# Sensor_Acquisition_Board_Rev4.net
KiCad netlist of a schematic drawn in EAGLE
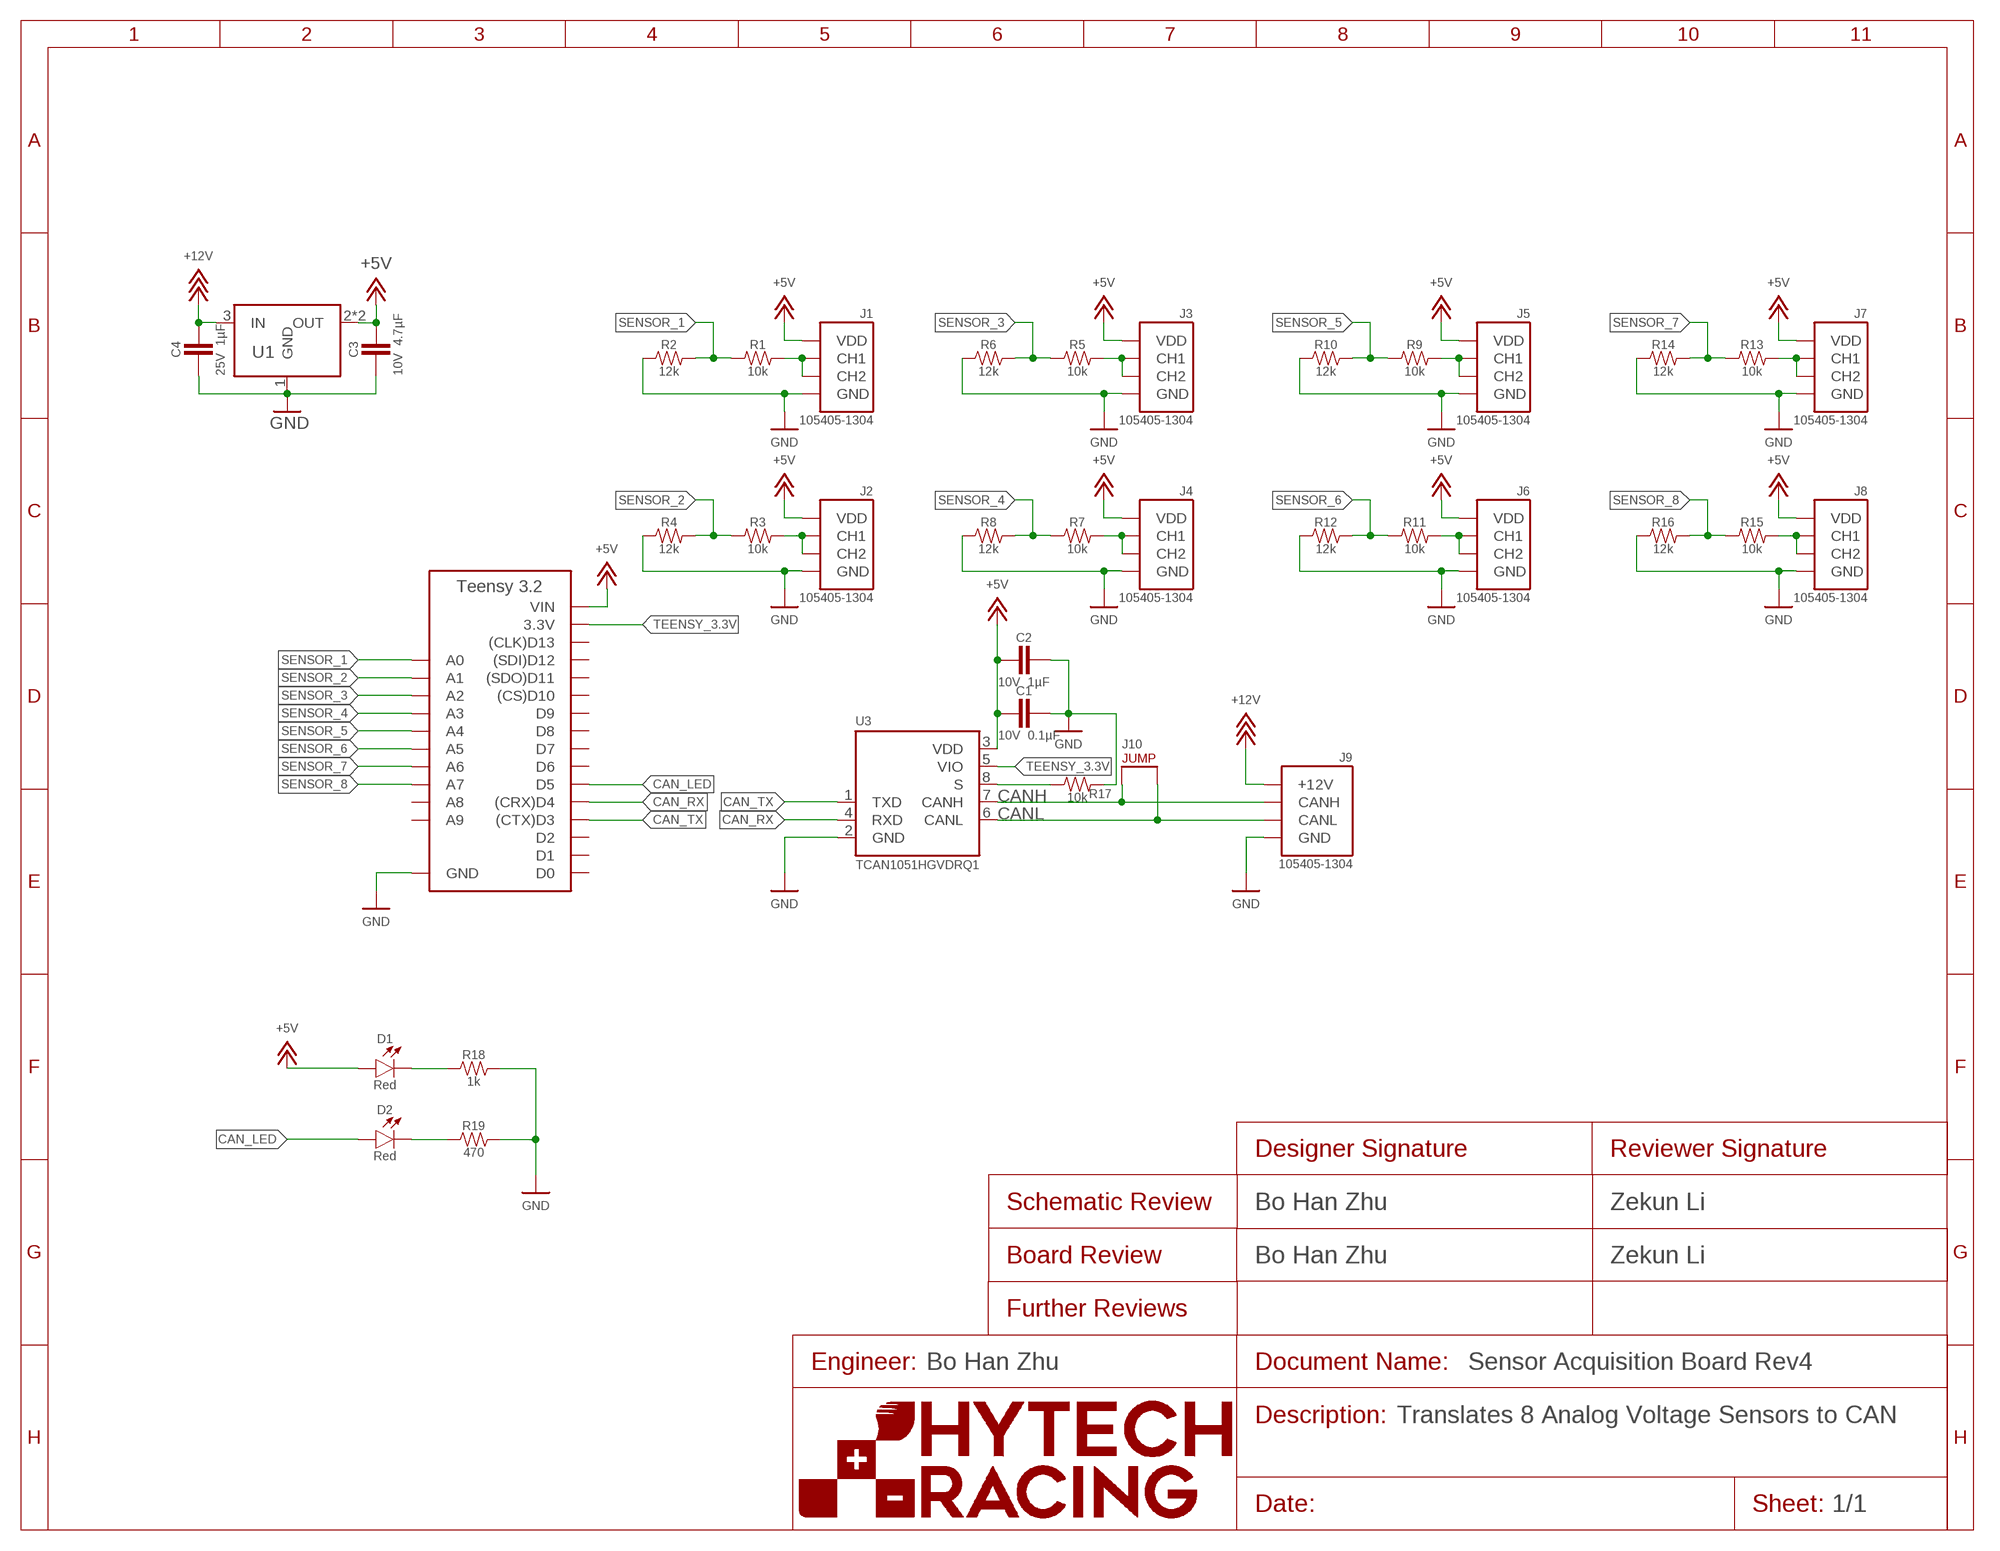
[diagram p0: schematic, sheet 1]

(export (version "E")
  (design (tool "Eeschema 10.0.6"))
  (components
    (comp (ref "A1")
      (value "TEENSY_3.2")
      (footprint "eagle-import:TEENSY_SHORT")
      (libsource (lib "eagle-import") (part "TEENSY_3.2"))
    )
    (comp (ref "C1")
      (value "CAPACITOR_0603_10V_0.1UF")
      (footprint "eagle-import:0603-CAP")
      (fields
        (field (name "CAPACITANCE") "0.1µF")
        (field (name "MANUFACTURER") "Vishay Vitramon")
        (field (name "MPN") "VJ0603Y104JXQPW1BC")
        (field (name "TOLERANCE") "5%")
        (field (name "VOLTAGE") "10V")
      )
      (libsource (lib "eagle-import") (part "CAPACITOR_?_060310V_0.1UF"))
    )
    (comp (ref "C2")
      (value "CAPACITOR_0603_10V_1UF")
      (footprint "eagle-import:0603-CAP")
      (fields
        (field (name "CAPACITANCE") "1µF")
        (field (name "MANUFACTURER") "Yageo")
        (field (name "MPN") "CC0603KRX7R6BB105")
        (field (name "TOLERANCE") "10%")
        (field (name "VOLTAGE") "10V")
      )
      (libsource (lib "eagle-import") (part "CAPACITOR_?_060310V_1UF"))
    )
    (comp (ref "C3")
      (value "CAPACITOR_0603_10V_4.7UF")
      (footprint "eagle-import:0603-CAP")
      (fields
        (field (name "CAPACITANCE") "4.7µF")
        (field (name "MANUFACTURER") "Samsung Electro-Mechanics")
        (field (name "MPN") "CL10A475KP8NNNC")
        (field (name "TOLERANCE") "10%")
        (field (name "VOLTAGE") "10V")
      )
      (libsource (lib "eagle-import") (part "CAPACITOR_?_060310V_4.7UF"))
    )
    (comp (ref "C4")
      (value "CAPACITOR_0603_25V_1UF")
      (footprint "eagle-import:0603-CAP")
      (fields
        (field (name "CAPACITANCE") "1µF")
        (field (name "MANUFACTURER") "Samsung Electro-Mechanics")
        (field (name "MPN") "CL10B105KA8NNNC")
        (field (name "TOLERANCE") "10%")
        (field (name "VOLTAGE") "25V")
      )
      (libsource (lib "eagle-import") (part "CAPACITOR_?_060325V_1UF"))
    )
    (comp (ref "D1")
      (value "LED_0603_RED")
      (footprint "eagle-import:0603-LED")
      (fields
        (field (name "COLOR") "Red")
        (field (name "MANUFACTURER") "Kingbright")
        (field (name "MPN") "APT1608SECK/J3-PRV")
      )
      (libsource (lib "eagle-import") (part "LED_?_0603RED"))
    )
    (comp (ref "D2")
      (value "LED_0603_RED")
      (footprint "eagle-import:0603-LED")
      (fields
        (field (name "COLOR") "Red")
        (field (name "MANUFACTURER") "Kingbright")
        (field (name "MPN") "APT1608SECK/J3-PRV")
      )
      (libsource (lib "eagle-import") (part "LED_?_0603RED"))
    )
    (comp (ref "J1")
      (value "CONNECTOR-SENSOR_NF_S_RA_BLACK")
      (footprint "eagle-import:MOLEX_NANOFIT_SMD_RIGHTANGLE_04")
      (fields (field (name "MANUFACTURER") "Molex") (field (name "MPN") "105405-1304"))
      (libsource (lib "eagle-import") (part "CONNECTOR-SENSOR_?_NF_S_RABLACK"))
    )
    (comp (ref "J2")
      (value "CONNECTOR-SENSOR_NF_S_RA_BLACK")
      (footprint "eagle-import:MOLEX_NANOFIT_SMD_RIGHTANGLE_04")
      (fields (field (name "MANUFACTURER") "Molex") (field (name "MPN") "105405-1304"))
      (libsource (lib "eagle-import") (part "CONNECTOR-SENSOR_?_NF_S_RABLACK"))
    )
    (comp (ref "J3")
      (value "CONNECTOR-SENSOR_NF_S_RA_BLACK")
      (footprint "eagle-import:MOLEX_NANOFIT_SMD_RIGHTANGLE_04")
      (fields (field (name "MANUFACTURER") "Molex") (field (name "MPN") "105405-1304"))
      (libsource (lib "eagle-import") (part "CONNECTOR-SENSOR_?_NF_S_RABLACK"))
    )
    (comp (ref "J4")
      (value "CONNECTOR-SENSOR_NF_S_RA_BLACK")
      (footprint "eagle-import:MOLEX_NANOFIT_SMD_RIGHTANGLE_04")
      (fields (field (name "MANUFACTURER") "Molex") (field (name "MPN") "105405-1304"))
      (libsource (lib "eagle-import") (part "CONNECTOR-SENSOR_?_NF_S_RABLACK"))
    )
    (comp (ref "J5")
      (value "CONNECTOR-SENSOR_NF_S_RA_BLACK")
      (footprint "eagle-import:MOLEX_NANOFIT_SMD_RIGHTANGLE_04")
      (fields (field (name "MANUFACTURER") "Molex") (field (name "MPN") "105405-1304"))
      (libsource (lib "eagle-import") (part "CONNECTOR-SENSOR_?_NF_S_RABLACK"))
    )
    (comp (ref "J6")
      (value "CONNECTOR-SENSOR_NF_S_RA_BLACK")
      (footprint "eagle-import:MOLEX_NANOFIT_SMD_RIGHTANGLE_04")
      (fields (field (name "MANUFACTURER") "Molex") (field (name "MPN") "105405-1304"))
      (libsource (lib "eagle-import") (part "CONNECTOR-SENSOR_?_NF_S_RABLACK"))
    )
    (comp (ref "J7")
      (value "CONNECTOR-SENSOR_NF_S_RA_BLACK")
      (footprint "eagle-import:MOLEX_NANOFIT_SMD_RIGHTANGLE_04")
      (fields (field (name "MANUFACTURER") "Molex") (field (name "MPN") "105405-1304"))
      (libsource (lib "eagle-import") (part "CONNECTOR-SENSOR_?_NF_S_RABLACK"))
    )
    (comp (ref "J8")
      (value "CONNECTOR-SENSOR_NF_S_RA_BLACK")
      (footprint "eagle-import:MOLEX_NANOFIT_SMD_RIGHTANGLE_04")
      (fields (field (name "MANUFACTURER") "Molex") (field (name "MPN") "105405-1304"))
      (libsource (lib "eagle-import") (part "CONNECTOR-SENSOR_?_NF_S_RABLACK"))
    )
    (comp (ref "J9")
      (value "CONNECTOR-CAN_NF_S_RA_BLACK")
      (footprint "eagle-import:MOLEX_NANOFIT_SMD_RIGHTANGLE_04")
      (fields (field (name "MANUFACTURER") "Molex") (field (name "MPN") "105405-1304"))
      (libsource (lib "eagle-import") (part "CONNECTOR-CAN_?_NF_S_RABLACK"))
    )
    (comp (ref "J10")
      (value "JUMPER_1X02_")
      (footprint "eagle-import:1X02")
      (libsource (lib "eagle-import") (part "JUMPER_?_1X02"))
    )
    (comp (ref "R1")
      (value "RESISTOR_0603_10K")
      (footprint "eagle-import:0603-RES")
      (fields
        (field (name "MANUFACTURER") "Yageo")
        (field (name "MPN") "RC0603FR-0710KL")
        (field (name "POWER") "0.1W")
        (field (name "RESISTANCE") "10k")
      )
      (libsource (lib "eagle-import") (part "RESISTOR_?_060310K"))
    )
    (comp (ref "R2")
      (value "RESISTOR_0603_12K")
      (footprint "eagle-import:0603-RES")
      (fields
        (field (name "MANUFACTURER") "Yageo")
        (field (name "MPN") "RC0603FR-0712KL")
        (field (name "POWER") "0.1W")
        (field (name "RESISTANCE") "12k")
      )
      (libsource (lib "eagle-import") (part "RESISTOR_?_060312K"))
    )
    (comp (ref "R3")
      (value "RESISTOR_0603_10K")
      (footprint "eagle-import:0603-RES")
      (fields
        (field (name "MANUFACTURER") "Yageo")
        (field (name "MPN") "RC0603FR-0710KL")
        (field (name "POWER") "0.1W")
        (field (name "RESISTANCE") "10k")
      )
      (libsource (lib "eagle-import") (part "RESISTOR_?_060310K"))
    )
    (comp (ref "R4")
      (value "RESISTOR_0603_12K")
      (footprint "eagle-import:0603-RES")
      (fields
        (field (name "MANUFACTURER") "Yageo")
        (field (name "MPN") "RC0603FR-0712KL")
        (field (name "POWER") "0.1W")
        (field (name "RESISTANCE") "12k")
      )
      (libsource (lib "eagle-import") (part "RESISTOR_?_060312K"))
    )
    (comp (ref "R5")
      (value "RESISTOR_0603_10K")
      (footprint "eagle-import:0603-RES")
      (fields
        (field (name "MANUFACTURER") "Yageo")
        (field (name "MPN") "RC0603FR-0710KL")
        (field (name "POWER") "0.1W")
        (field (name "RESISTANCE") "10k")
      )
      (libsource (lib "eagle-import") (part "RESISTOR_?_060310K"))
    )
    (comp (ref "R6")
      (value "RESISTOR_0603_12K")
      (footprint "eagle-import:0603-RES")
      (fields
        (field (name "MANUFACTURER") "Yageo")
        (field (name "MPN") "RC0603FR-0712KL")
        (field (name "POWER") "0.1W")
        (field (name "RESISTANCE") "12k")
      )
      (libsource (lib "eagle-import") (part "RESISTOR_?_060312K"))
    )
    (comp (ref "R7")
      (value "RESISTOR_0603_10K")
      (footprint "eagle-import:0603-RES")
      (fields
        (field (name "MANUFACTURER") "Yageo")
        (field (name "MPN") "RC0603FR-0710KL")
        (field (name "POWER") "0.1W")
        (field (name "RESISTANCE") "10k")
      )
      (libsource (lib "eagle-import") (part "RESISTOR_?_060310K"))
    )
    (comp (ref "R8")
      (value "RESISTOR_0603_12K")
      (footprint "eagle-import:0603-RES")
      (fields
        (field (name "MANUFACTURER") "Yageo")
        (field (name "MPN") "RC0603FR-0712KL")
        (field (name "POWER") "0.1W")
        (field (name "RESISTANCE") "12k")
      )
      (libsource (lib "eagle-import") (part "RESISTOR_?_060312K"))
    )
    (comp (ref "R9")
      (value "RESISTOR_0603_10K")
      (footprint "eagle-import:0603-RES")
      (fields
        (field (name "MANUFACTURER") "Yageo")
        (field (name "MPN") "RC0603FR-0710KL")
        (field (name "POWER") "0.1W")
        (field (name "RESISTANCE") "10k")
      )
      (libsource (lib "eagle-import") (part "RESISTOR_?_060310K"))
    )
    (comp (ref "R10")
      (value "RESISTOR_0603_12K")
      (footprint "eagle-import:0603-RES")
      (fields
        (field (name "MANUFACTURER") "Yageo")
        (field (name "MPN") "RC0603FR-0712KL")
        (field (name "POWER") "0.1W")
        (field (name "RESISTANCE") "12k")
      )
      (libsource (lib "eagle-import") (part "RESISTOR_?_060312K"))
    )
    (comp (ref "R11")
      (value "RESISTOR_0603_10K")
      (footprint "eagle-import:0603-RES")
      (fields
        (field (name "MANUFACTURER") "Yageo")
        (field (name "MPN") "RC0603FR-0710KL")
        (field (name "POWER") "0.1W")
        (field (name "RESISTANCE") "10k")
      )
      (libsource (lib "eagle-import") (part "RESISTOR_?_060310K"))
    )
    (comp (ref "R12")
      (value "RESISTOR_0603_12K")
      (footprint "eagle-import:0603-RES")
      (fields
        (field (name "MANUFACTURER") "Yageo")
        (field (name "MPN") "RC0603FR-0712KL")
        (field (name "POWER") "0.1W")
        (field (name "RESISTANCE") "12k")
      )
      (libsource (lib "eagle-import") (part "RESISTOR_?_060312K"))
    )
    (comp (ref "R13")
      (value "RESISTOR_0603_10K")
      (footprint "eagle-import:0603-RES")
      (fields
        (field (name "MANUFACTURER") "Yageo")
        (field (name "MPN") "RC0603FR-0710KL")
        (field (name "POWER") "0.1W")
        (field (name "RESISTANCE") "10k")
      )
      (libsource (lib "eagle-import") (part "RESISTOR_?_060310K"))
    )
    (comp (ref "R14")
      (value "RESISTOR_0603_12K")
      (footprint "eagle-import:0603-RES")
      (fields
        (field (name "MANUFACTURER") "Yageo")
        (field (name "MPN") "RC0603FR-0712KL")
        (field (name "POWER") "0.1W")
        (field (name "RESISTANCE") "12k")
      )
      (libsource (lib "eagle-import") (part "RESISTOR_?_060312K"))
    )
    (comp (ref "R15")
      (value "RESISTOR_0603_10K")
      (footprint "eagle-import:0603-RES")
      (fields
        (field (name "MANUFACTURER") "Yageo")
        (field (name "MPN") "RC0603FR-0710KL")
        (field (name "POWER") "0.1W")
        (field (name "RESISTANCE") "10k")
      )
      (libsource (lib "eagle-import") (part "RESISTOR_?_060310K"))
    )
    (comp (ref "R16")
      (value "RESISTOR_0603_12K")
      (footprint "eagle-import:0603-RES")
      (fields
        (field (name "MANUFACTURER") "Yageo")
        (field (name "MPN") "RC0603FR-0712KL")
        (field (name "POWER") "0.1W")
        (field (name "RESISTANCE") "12k")
      )
      (libsource (lib "eagle-import") (part "RESISTOR_?_060312K"))
    )
    (comp (ref "R17")
      (value "RESISTOR_0603_10K")
      (footprint "eagle-import:0603-RES")
      (fields
        (field (name "MANUFACTURER") "Yageo")
        (field (name "MPN") "RC0603FR-0710KL")
        (field (name "POWER") "0.1W")
        (field (name "RESISTANCE") "10k")
      )
      (libsource (lib "eagle-import") (part "RESISTOR_?_060310K"))
    )
    (comp (ref "R18")
      (value "RESISTOR_0603_1K")
      (footprint "eagle-import:0603-RES")
      (fields
        (field (name "MANUFACTURER") "Yageo")
        (field (name "MPN") "RC0603FR-071KL")
        (field (name "POWER") "0.1W")
        (field (name "RESISTANCE") "1k")
      )
      (libsource (lib "eagle-import") (part "RESISTOR_?_06031K"))
    )
    (comp (ref "R19")
      (value "RESISTOR_0603_470")
      (footprint "eagle-import:0603-RES")
      (fields
        (field (name "MANUFACTURER") "Panasonic Electronic Components")
        (field (name "MPN") "ERJ-PA3F4700V")
        (field (name "POWER") "0.25W")
        (field (name "RESISTANCE") "470")
      )
      (libsource (lib "eagle-import") (part "RESISTOR_?_0603470"))
    )
    (comp (ref "U1")
      (value "VOLTAGE_REGULATOR_SOT223_5V")
      (footprint "eagle-import:SOT223")
      (fields (field (name "MANUFACTURER") "STMicroelectronics") (field (name "MPN") "LDL1117S50R"))
      (libsource (lib "eagle-import") (part "VOLTAGE_REGULATOR_?_SOT2235V"))
    )
    (comp (ref "U3")
      (value "TCAN1051HQV-Q1")
      (footprint "eagle-import:SOIC-08(NARROW,0.15_)")
      (fields (field (name "MANUFACTURER") "Texas Instruments") (field (name "MPN") "TCAN1051HGVDRQ1"))
      (libsource (lib "eagle-import") (part "TCAN1051V-Q1HQ"))
    )
  )
  (nets
    (net (code "1") (name "+5V") (class "Default")
      (node (ref "A1") (pin "VIN") (pinfunction "VIN_VIN") (pintype "power_in"))
      (node (ref "C1") (pin "2") (pinfunction "2_2") (pintype "passive"))
      (node (ref "C2") (pin "2") (pinfunction "2_2") (pintype "passive"))
      (node (ref "C3") (pin "1") (pinfunction "1_1") (pintype "passive"))
      (node (ref "D1") (pin "2") (pinfunction "A_2") (pintype "passive"))
      (node (ref "J1") (pin "1") (pinfunction "VDD_1") (pintype "power_in"))
      (node (ref "J2") (pin "1") (pinfunction "VDD_1") (pintype "power_in"))
      (node (ref "J3") (pin "1") (pinfunction "VDD_1") (pintype "power_in"))
      (node (ref "J4") (pin "1") (pinfunction "VDD_1") (pintype "power_in"))
      (node (ref "J5") (pin "1") (pinfunction "VDD_1") (pintype "power_in"))
      (node (ref "J6") (pin "1") (pinfunction "VDD_1") (pintype "power_in"))
      (node (ref "J7") (pin "1") (pinfunction "VDD_1") (pintype "power_in"))
      (node (ref "J8") (pin "1") (pinfunction "VDD_1") (pintype "power_in"))
      (node (ref "U1") (pin "2") (pinfunction "OUT_2") (pintype "power_in"))
      (node (ref "U1") (pin "4") (pinfunction "OUT_4") (pintype "power_in"))
      (node (ref "U3") (pin "3") (pinfunction "VDD_3") (pintype "power_in"))
    )
    (net (code "2") (name "+12V") (class "Default")
      (node (ref "C4") (pin "1") (pinfunction "1_1") (pintype "passive"))
      (node (ref "J9") (pin "1") (pinfunction "+12V_1") (pintype "power_in"))
      (node (ref "U1") (pin "3") (pinfunction "IN_3") (pintype "power_in"))
    )
    (net (code "3") (name "/CANH") (class "Default")
      (node (ref "J10") (pin "1") (pinfunction "P$1_1") (pintype "passive"))
      (node (ref "J9") (pin "4") (pinfunction "CANH_4") (pintype "bidirectional"))
      (node (ref "U3") (pin "7") (pinfunction "CANH_7") (pintype "output"))
    )
    (net (code "4") (name "/CANL") (class "Default")
      (node (ref "J10") (pin "2") (pinfunction "P$2_2") (pintype "passive"))
      (node (ref "J9") (pin "3") (pinfunction "CANL_3") (pintype "bidirectional"))
      (node (ref "U3") (pin "6") (pinfunction "CANL_6") (pintype "bidirectional"))
    )
    (net (code "5") (name "CAN_LED") (class "Default")
      (node (ref "A1") (pin "D5") (pinfunction "D5_D5") (pintype "bidirectional"))
      (node (ref "D2") (pin "2") (pinfunction "A_2") (pintype "passive"))
    )
    (net (code "6") (name "CAN_RX") (class "Default")
      (node (ref "A1") (pin "D4") (pinfunction "(CRX)D4_D4") (pintype "bidirectional"))
      (node (ref "U3") (pin "4") (pinfunction "RXD_4") (pintype "output"))
    )
    (net (code "7") (name "CAN_TX") (class "Default")
      (node (ref "A1") (pin "D3") (pinfunction "(CTX)D3_D3") (pintype "bidirectional"))
      (node (ref "U3") (pin "1") (pinfunction "TXD_1") (pintype "input"))
    )
    (net (code "8") (name "GND") (class "Default")
      (node (ref "A1") (pin "AGND/GND") (pinfunction "GND_AGND/GND") (pintype "power_in"))
      (node (ref "A1") (pin "GND") (pinfunction "GND_GND") (pintype "power_in"))
      (node (ref "C1") (pin "1") (pinfunction "1_1") (pintype "passive"))
      (node (ref "C2") (pin "1") (pinfunction "1_1") (pintype "passive"))
      (node (ref "C3") (pin "2") (pinfunction "2_2") (pintype "passive"))
      (node (ref "C4") (pin "2") (pinfunction "2_2") (pintype "passive"))
      (node (ref "J1") (pin "2") (pinfunction "GND_2") (pintype "power_in"))
      (node (ref "J2") (pin "2") (pinfunction "GND_2") (pintype "power_in"))
      (node (ref "J3") (pin "2") (pinfunction "GND_2") (pintype "power_in"))
      (node (ref "J4") (pin "2") (pinfunction "GND_2") (pintype "power_in"))
      (node (ref "J5") (pin "2") (pinfunction "GND_2") (pintype "power_in"))
      (node (ref "J6") (pin "2") (pinfunction "GND_2") (pintype "power_in"))
      (node (ref "J7") (pin "2") (pinfunction "GND_2") (pintype "power_in"))
      (node (ref "J8") (pin "2") (pinfunction "GND_2") (pintype "power_in"))
      (node (ref "J9") (pin "2") (pinfunction "GND_2") (pintype "power_in"))
      (node (ref "R10") (pin "1") (pinfunction "1_1") (pintype "passive"))
      (node (ref "R12") (pin "1") (pinfunction "1_1") (pintype "passive"))
      (node (ref "R14") (pin "1") (pinfunction "1_1") (pintype "passive"))
      (node (ref "R16") (pin "1") (pinfunction "1_1") (pintype "passive"))
      (node (ref "R17") (pin "2") (pinfunction "2_2") (pintype "passive"))
      (node (ref "R18") (pin "2") (pinfunction "2_2") (pintype "passive"))
      (node (ref "R19") (pin "2") (pinfunction "2_2") (pintype "passive"))
      (node (ref "R2") (pin "1") (pinfunction "1_1") (pintype "passive"))
      (node (ref "R4") (pin "1") (pinfunction "1_1") (pintype "passive"))
      (node (ref "R6") (pin "1") (pinfunction "1_1") (pintype "passive"))
      (node (ref "R8") (pin "1") (pinfunction "1_1") (pintype "passive"))
      (node (ref "U1") (pin "1") (pinfunction "GND_1") (pintype "power_in"))
      (node (ref "U3") (pin "2") (pinfunction "GND_2") (pintype "power_in"))
    )
    (net (code "9") (name "Net-(D1-C)") (class "Default")
      (node (ref "D1") (pin "1") (pinfunction "C_1") (pintype "passive"))
      (node (ref "R18") (pin "1") (pinfunction "1_1") (pintype "passive"))
    )
    (net (code "10") (name "Net-(D2-C)") (class "Default")
      (node (ref "D2") (pin "1") (pinfunction "C_1") (pintype "passive"))
      (node (ref "R19") (pin "1") (pinfunction "1_1") (pintype "passive"))
    )
    (net (code "11") (name "Net-(J1-CH1)") (class "Default")
      (node (ref "J1") (pin "3") (pinfunction "CH1_3") (pintype "output"))
      (node (ref "J1") (pin "4") (pinfunction "CH2_4") (pintype "output"))
      (node (ref "R1") (pin "2") (pinfunction "2_2") (pintype "passive"))
    )
    (net (code "12") (name "Net-(J2-CH1)") (class "Default")
      (node (ref "J2") (pin "3") (pinfunction "CH1_3") (pintype "output"))
      (node (ref "J2") (pin "4") (pinfunction "CH2_4") (pintype "output"))
      (node (ref "R3") (pin "2") (pinfunction "2_2") (pintype "passive"))
    )
    (net (code "13") (name "Net-(J3-CH1)") (class "Default")
      (node (ref "J3") (pin "3") (pinfunction "CH1_3") (pintype "output"))
      (node (ref "J3") (pin "4") (pinfunction "CH2_4") (pintype "output"))
      (node (ref "R5") (pin "2") (pinfunction "2_2") (pintype "passive"))
    )
    (net (code "14") (name "Net-(J4-CH1)") (class "Default")
      (node (ref "J4") (pin "3") (pinfunction "CH1_3") (pintype "output"))
      (node (ref "J4") (pin "4") (pinfunction "CH2_4") (pintype "output"))
      (node (ref "R7") (pin "2") (pinfunction "2_2") (pintype "passive"))
    )
    (net (code "15") (name "Net-(J5-CH1)") (class "Default")
      (node (ref "J5") (pin "3") (pinfunction "CH1_3") (pintype "output"))
      (node (ref "J5") (pin "4") (pinfunction "CH2_4") (pintype "output"))
      (node (ref "R9") (pin "2") (pinfunction "2_2") (pintype "passive"))
    )
    (net (code "16") (name "Net-(J6-CH1)") (class "Default")
      (node (ref "J6") (pin "3") (pinfunction "CH1_3") (pintype "output"))
      (node (ref "J6") (pin "4") (pinfunction "CH2_4") (pintype "output"))
      (node (ref "R11") (pin "2") (pinfunction "2_2") (pintype "passive"))
    )
    (net (code "17") (name "Net-(J7-CH1)") (class "Default")
      (node (ref "J7") (pin "3") (pinfunction "CH1_3") (pintype "output"))
      (node (ref "J7") (pin "4") (pinfunction "CH2_4") (pintype "output"))
      (node (ref "R13") (pin "2") (pinfunction "2_2") (pintype "passive"))
    )
    (net (code "18") (name "Net-(J8-CH1)") (class "Default")
      (node (ref "J8") (pin "3") (pinfunction "CH1_3") (pintype "output"))
      (node (ref "J8") (pin "4") (pinfunction "CH2_4") (pintype "output"))
      (node (ref "R15") (pin "2") (pinfunction "2_2") (pintype "passive"))
    )
    (net (code "19") (name "Net-(U3-S)") (class "Default")
      (node (ref "R17") (pin "1") (pinfunction "1_1") (pintype "passive"))
      (node (ref "U3") (pin "8") (pinfunction "S_8") (pintype "input"))
    )
    (net (code "20") (name "SENSOR_1") (class "Default")
      (node (ref "A1") (pin "D14") (pinfunction "A0_D14") (pintype "bidirectional"))
      (node (ref "R1") (pin "1") (pinfunction "1_1") (pintype "passive"))
      (node (ref "R2") (pin "2") (pinfunction "2_2") (pintype "passive"))
    )
    (net (code "21") (name "SENSOR_2") (class "Default")
      (node (ref "A1") (pin "D15") (pinfunction "A1_D15") (pintype "bidirectional"))
      (node (ref "R3") (pin "1") (pinfunction "1_1") (pintype "passive"))
      (node (ref "R4") (pin "2") (pinfunction "2_2") (pintype "passive"))
    )
    (net (code "22") (name "SENSOR_3") (class "Default")
      (node (ref "A1") (pin "D16") (pinfunction "A2_D16") (pintype "bidirectional"))
      (node (ref "R5") (pin "1") (pinfunction "1_1") (pintype "passive"))
      (node (ref "R6") (pin "2") (pinfunction "2_2") (pintype "passive"))
    )
    (net (code "23") (name "SENSOR_4") (class "Default")
      (node (ref "A1") (pin "D17") (pinfunction "A3_D17") (pintype "bidirectional"))
      (node (ref "R7") (pin "1") (pinfunction "1_1") (pintype "passive"))
      (node (ref "R8") (pin "2") (pinfunction "2_2") (pintype "passive"))
    )
    (net (code "24") (name "SENSOR_5") (class "Default")
      (node (ref "A1") (pin "D18") (pinfunction "A4_D18") (pintype "bidirectional"))
      (node (ref "R10") (pin "2") (pinfunction "2_2") (pintype "passive"))
      (node (ref "R9") (pin "1") (pinfunction "1_1") (pintype "passive"))
    )
    (net (code "25") (name "SENSOR_6") (class "Default")
      (node (ref "A1") (pin "D19") (pinfunction "A5_D19") (pintype "bidirectional"))
      (node (ref "R11") (pin "1") (pinfunction "1_1") (pintype "passive"))
      (node (ref "R12") (pin "2") (pinfunction "2_2") (pintype "passive"))
    )
    (net (code "26") (name "SENSOR_7") (class "Default")
      (node (ref "A1") (pin "D20") (pinfunction "A6_D20") (pintype "bidirectional"))
      (node (ref "R13") (pin "1") (pinfunction "1_1") (pintype "passive"))
      (node (ref "R14") (pin "2") (pinfunction "2_2") (pintype "passive"))
    )
    (net (code "27") (name "SENSOR_8") (class "Default")
      (node (ref "A1") (pin "D21") (pinfunction "A7_D21") (pintype "bidirectional"))
      (node (ref "R15") (pin "1") (pinfunction "1_1") (pintype "passive"))
      (node (ref "R16") (pin "2") (pinfunction "2_2") (pintype "passive"))
    )
    (net (code "28") (name "TEENSY_3.3V") (class "Default")
      (node (ref "A1") (pin "3.3V") (pinfunction "3.3V_3.3V") (pintype "power_in"))
      (node (ref "U3") (pin "5") (pinfunction "VIO_5") (pintype "power_in"))
    )
    (net (code "29") (name "unconnected-(A1-(CLK)D13-PadD13)") (class "Default")
      (node (ref "A1") (pin "D13") (pinfunction "(CLK)D13_D13") (pintype "bidirectional"))
    )
    (net (code "30") (name "unconnected-(A1-(CS)D10-PadD10)") (class "Default")
      (node (ref "A1") (pin "D10") (pinfunction "(CS)D10_D10") (pintype "bidirectional"))
    )
    (net (code "31") (name "unconnected-(A1-(SDI)D12-PadD12)") (class "Default")
      (node (ref "A1") (pin "D12") (pinfunction "(SDI)D12_D12") (pintype "bidirectional"))
    )
    (net (code "32") (name "unconnected-(A1-(SDO)D11-PadD11)") (class "Default")
      (node (ref "A1") (pin "D11") (pinfunction "(SDO)D11_D11") (pintype "bidirectional"))
    )
    (net (code "33") (name "unconnected-(A1-A8-PadD22)") (class "Default")
      (node (ref "A1") (pin "D22") (pinfunction "A8_D22") (pintype "bidirectional"))
    )
    (net (code "34") (name "unconnected-(A1-A9-PadD23)") (class "Default")
      (node (ref "A1") (pin "D23") (pinfunction "A9_D23") (pintype "bidirectional"))
    )
    (net (code "35") (name "unconnected-(A1-PadD0)") (class "Default")
      (node (ref "A1") (pin "D0") (pinfunction "D0_D0") (pintype "bidirectional"))
    )
    (net (code "36") (name "unconnected-(A1-PadD1)") (class "Default")
      (node (ref "A1") (pin "D1") (pinfunction "D1_D1") (pintype "bidirectional"))
    )
    (net (code "37") (name "unconnected-(A1-PadD2)") (class "Default")
      (node (ref "A1") (pin "D2") (pinfunction "D2_D2") (pintype "bidirectional"))
    )
    (net (code "38") (name "unconnected-(A1-PadD6)") (class "Default")
      (node (ref "A1") (pin "D6") (pinfunction "D6_D6") (pintype "bidirectional"))
    )
    (net (code "39") (name "unconnected-(A1-PadD7)") (class "Default")
      (node (ref "A1") (pin "D7") (pinfunction "D7_D7") (pintype "bidirectional"))
    )
    (net (code "40") (name "unconnected-(A1-PadD8)") (class "Default")
      (node (ref "A1") (pin "D8") (pinfunction "D8_D8") (pintype "bidirectional"))
    )
    (net (code "41") (name "unconnected-(A1-PadD9)") (class "Default")
      (node (ref "A1") (pin "D9") (pinfunction "D9_D9") (pintype "bidirectional"))
    )
  )
)
